# 32-054.net
KiCad netlist of a schematic drawn in Altium Designer
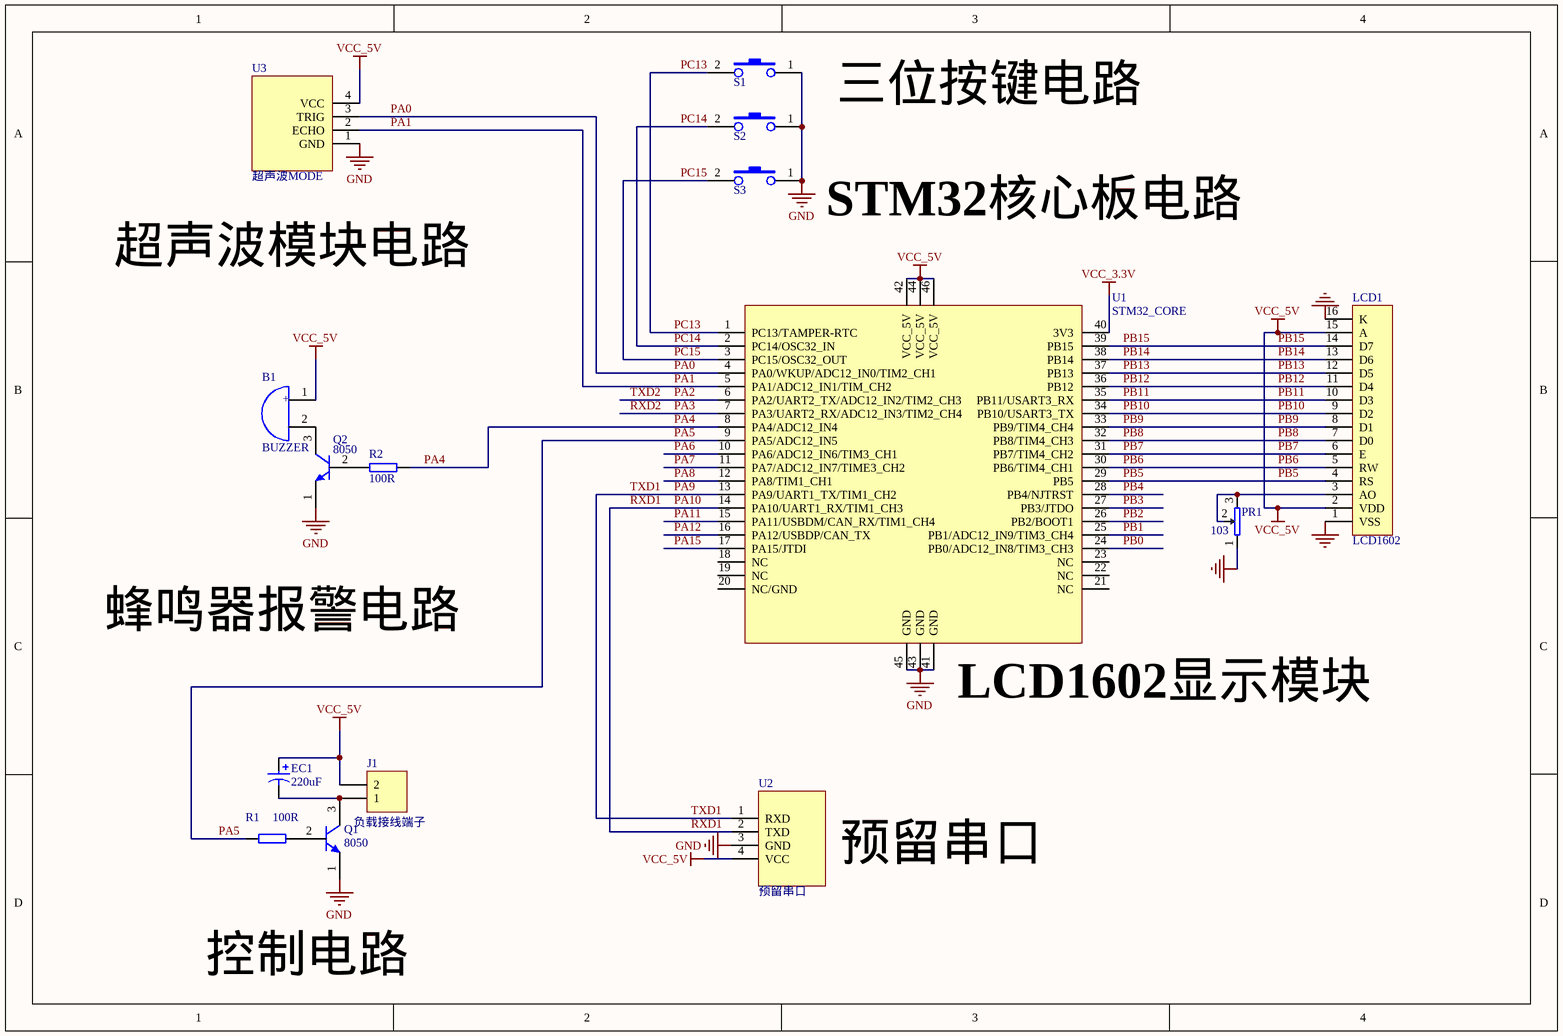
[diagram p0: 32-054原理图（源文件格式）.SchDoc]

(export (version "E")
  (design (tool "Eeschema 10.0.6"))
  (components
    (comp (ref "B1")
      (value "BUZZER")
      (footprint "BUZZERSOT_PLASTIC")
      (description "蜂鸣器")
      (libsource (lib "参考") (part "BUZZER"))
    )
    (comp (ref "EC1")
      (value "220uF")
      (footprint "RB.15/.3")
      (description "极性电容")
      (libsource (lib "参考") (part "CAP_EC"))
    )
    (comp (ref "J1")
      (value "负载接线端子")
      (footprint "XH-2.54-2P")
      (description "接线端子2芯")
      (fields (field (name "PUBLISHER") "Altium Limited"))
      (libsource (lib "参考") (part "CON2"))
    )
    (comp (ref "LCD1")
      (value "LCD1602")
      (footprint "LCD1602")
      (description "LCD1602液晶")
      (libsource (lib "参考") (part "LCD1602"))
    )
    (comp (ref "PR1")
      (value "103")
      (footprint "WH06-2")
      (description "电位器")
      (libsource (lib "参考") (part "PR"))
    )
    (comp (ref "Q1")
      (value "8050")
      (footprint "TO-92")
      (description "三极管")
      (libsource (lib "参考") (part "9013"))
    )
    (comp (ref "Q2")
      (value "8050")
      (footprint "TO-92")
      (description "三极管")
      (libsource (lib "参考") (part "9013"))
    )
    (comp (ref "R1")
      (value "100R")
      (footprint "AXIAL0.3")
      (description "电阻")
      (libsource (lib "参考") (part "RES"))
    )
    (comp (ref "R2")
      (value "100R")
      (footprint "AXIAL0.3")
      (description "电阻")
      (libsource (lib "参考") (part "RES"))
    )
    (comp (ref "S1")
      (value "BUTTOM")
      (footprint "BUTTOM_6x6DIP")
      (description "按键")
      (libsource (lib "参考") (part "BUTTOM"))
    )
    (comp (ref "S2")
      (value "BUTTOM")
      (footprint "BUTTOM_6x6DIP")
      (description "按键")
      (libsource (lib "参考") (part "BUTTOM"))
    )
    (comp (ref "S3")
      (value "BUTTOM")
      (footprint "BUTTOM_6x6DIP")
      (description "按键")
      (libsource (lib "参考") (part "BUTTOM"))
    )
    (comp (ref "U1")
      (value "STM32_CORE")
      (footprint "STM32_CORE")
      (description "STM32核心板")
      (libsource (lib "参考") (part "STM32_CORE"))
    )
    (comp (ref "U2") (value "预留串口") (footprint "蓝牙MODE竖放") (libsource (lib "参考") (part "蓝牙MODE")))
    (comp (ref "U3")
      (value "超声波MODE")
      (footprint "超声波MODE")
      (description "超声波模块")
      (libsource (lib "参考") (part "超声波MODE"))
    )
  )
  (nets
    (net (code "1") (name "/PA0") (class "Default")
      (node (ref "U1") (pin "4") (pinfunction "PA0/WKUP/ADC12_IN0/TIM2_CH1_4") (pintype "passive"))
      (node (ref "U3") (pin "3") (pinfunction "TRIG_3") (pintype "passive"))
    )
    (net (code "2") (name "/PA1") (class "Default")
      (node (ref "U1") (pin "5") (pinfunction "PA1/ADC12_IN1/TIM_CH2_5") (pintype "passive"))
      (node (ref "U3") (pin "2") (pinfunction "ECHO_2") (pintype "passive"))
    )
    (net (code "3") (name "/PA2") (class "Default")
      (node (ref "U1") (pin "6") (pinfunction "PA2/UART2_TX/ADC12_IN2/TIM2_CH3_6") (pintype "passive"))
    )
    (net (code "4") (name "/PA3") (class "Default")
      (node (ref "U1") (pin "7") (pinfunction "PA3/UART2_RX/ADC12_IN3/TIM2_CH4_7") (pintype "passive"))
    )
    (net (code "5") (name "/PA4") (class "Default")
      (node (ref "R2") (pin "2") (pinfunction "2_2") (pintype "passive"))
      (node (ref "U1") (pin "8") (pinfunction "PA4/ADC12_IN4_8") (pintype "passive"))
    )
    (net (code "6") (name "/PA5") (class "Default")
      (node (ref "R1") (pin "2") (pinfunction "2_2") (pintype "passive"))
      (node (ref "U1") (pin "9") (pinfunction "PA5/ADC12_IN5_9") (pintype "passive"))
    )
    (net (code "7") (name "/PA6") (class "Default")
      (node (ref "U1") (pin "10") (pinfunction "PA6/ADC12_IN6/TIM3_CH1_10") (pintype "passive"))
    )
    (net (code "8") (name "/PA7") (class "Default")
      (node (ref "U1") (pin "11") (pinfunction "PA7/ADC12_IN7/TIME3_CH2_11") (pintype "passive"))
    )
    (net (code "9") (name "/PA8") (class "Default")
      (node (ref "U1") (pin "12") (pinfunction "PA8/TIM1_CH1_12") (pintype "passive"))
    )
    (net (code "10") (name "/PA9") (class "Default")
      (node (ref "U1") (pin "13") (pinfunction "PA9/UART1_TX/TIM1_CH2_13") (pintype "passive"))
      (node (ref "U2") (pin "1") (pinfunction "RXD_1") (pintype "passive"))
    )
    (net (code "11") (name "/PA10") (class "Default")
      (node (ref "U1") (pin "14") (pinfunction "PA10/UART1_RX/TIM1_CH3_14") (pintype "passive"))
      (node (ref "U2") (pin "2") (pinfunction "TXD_2") (pintype "passive"))
    )
    (net (code "12") (name "/PA11") (class "Default")
      (node (ref "U1") (pin "15") (pinfunction "PA11/USBDM/CAN_RX/TIM1_CH4_15") (pintype "passive"))
    )
    (net (code "13") (name "/PA12") (class "Default")
      (node (ref "U1") (pin "16") (pinfunction "PA12/USBDP/CAN_TX_16") (pintype "passive"))
    )
    (net (code "14") (name "/PA15") (class "Default")
      (node (ref "U1") (pin "17") (pinfunction "PA15/JTDI_17") (pintype "passive"))
    )
    (net (code "15") (name "/PB0") (class "Default")
      (node (ref "U1") (pin "24") (pinfunction "PB0/ADC12_IN8/TIM3_CH3_24") (pintype "passive"))
    )
    (net (code "16") (name "/PB1") (class "Default")
      (node (ref "U1") (pin "25") (pinfunction "PB1/ADC12_IN9/TIM3_CH4_25") (pintype "passive"))
    )
    (net (code "17") (name "/PB2") (class "Default")
      (node (ref "U1") (pin "26") (pinfunction "PB2/BOOT1_26") (pintype "passive"))
    )
    (net (code "18") (name "/PB3") (class "Default")
      (node (ref "U1") (pin "27") (pinfunction "PB3/JTDO_27") (pintype "passive"))
    )
    (net (code "19") (name "/PB4") (class "Default")
      (node (ref "U1") (pin "28") (pinfunction "PB4/NJTRST_28") (pintype "passive"))
    )
    (net (code "20") (name "/PB5") (class "Default")
      (node (ref "LCD1") (pin "4") (pinfunction "RS_4") (pintype "passive"))
      (node (ref "U1") (pin "29") (pinfunction "PB5_29") (pintype "passive"))
    )
    (net (code "21") (name "/PB6") (class "Default")
      (node (ref "LCD1") (pin "5") (pinfunction "RW_5") (pintype "passive"))
      (node (ref "U1") (pin "30") (pinfunction "PB6/TIM4_CH1_30") (pintype "passive"))
    )
    (net (code "22") (name "/PB7") (class "Default")
      (node (ref "LCD1") (pin "6") (pinfunction "E_6") (pintype "passive"))
      (node (ref "U1") (pin "31") (pinfunction "PB7/TIM4_CH2_31") (pintype "passive"))
    )
    (net (code "23") (name "/PB8") (class "Default")
      (node (ref "LCD1") (pin "7") (pinfunction "D0_7") (pintype "passive"))
      (node (ref "U1") (pin "32") (pinfunction "PB8/TIM4_CH3_32") (pintype "passive"))
    )
    (net (code "24") (name "/PB9") (class "Default")
      (node (ref "LCD1") (pin "8") (pinfunction "D1_8") (pintype "passive"))
      (node (ref "U1") (pin "33") (pinfunction "PB9/TIM4_CH4_33") (pintype "passive"))
    )
    (net (code "25") (name "/PB10") (class "Default")
      (node (ref "LCD1") (pin "9") (pinfunction "D2_9") (pintype "passive"))
      (node (ref "U1") (pin "34") (pinfunction "PB10/USART3_TX_34") (pintype "passive"))
    )
    (net (code "26") (name "/PB11") (class "Default")
      (node (ref "LCD1") (pin "10") (pinfunction "D3_10") (pintype "passive"))
      (node (ref "U1") (pin "35") (pinfunction "PB11/USART3_RX_35") (pintype "passive"))
    )
    (net (code "27") (name "/PB12") (class "Default")
      (node (ref "LCD1") (pin "11") (pinfunction "D4_11") (pintype "passive"))
      (node (ref "U1") (pin "36") (pinfunction "PB12_36") (pintype "passive"))
    )
    (net (code "28") (name "/PB13") (class "Default")
      (node (ref "LCD1") (pin "12") (pinfunction "D5_12") (pintype "passive"))
      (node (ref "U1") (pin "37") (pinfunction "PB13_37") (pintype "passive"))
    )
    (net (code "29") (name "/PB14") (class "Default")
      (node (ref "LCD1") (pin "13") (pinfunction "D6_13") (pintype "passive"))
      (node (ref "U1") (pin "38") (pinfunction "PB14_38") (pintype "passive"))
    )
    (net (code "30") (name "/PB15") (class "Default")
      (node (ref "LCD1") (pin "14") (pinfunction "D7_14") (pintype "passive"))
      (node (ref "U1") (pin "39") (pinfunction "PB15_39") (pintype "passive"))
    )
    (net (code "31") (name "/PC13") (class "Default")
      (node (ref "S1") (pin "2") (pinfunction "2_2") (pintype "passive"))
      (node (ref "U1") (pin "1") (pinfunction "PC13/TAMPER-RTC_1") (pintype "passive"))
    )
    (net (code "32") (name "/PC14") (class "Default")
      (node (ref "S2") (pin "2") (pinfunction "2_2") (pintype "passive"))
      (node (ref "U1") (pin "2") (pinfunction "PC14/OSC32_IN_2") (pintype "passive"))
    )
    (net (code "33") (name "/PC15") (class "Default")
      (node (ref "S3") (pin "2") (pinfunction "2_2") (pintype "passive"))
      (node (ref "U1") (pin "3") (pinfunction "PC15/OSC32_OUT_3") (pintype "passive"))
    )
    (net (code "34") (name "GND") (class "Default")
      (node (ref "LCD1") (pin "1") (pinfunction "VSS_1") (pintype "passive"))
      (node (ref "LCD1") (pin "16") (pinfunction "K_16") (pintype "passive"))
      (node (ref "PR1") (pin "1") (pinfunction "1_1") (pintype "passive"))
      (node (ref "Q1") (pin "1") (pinfunction "1_1") (pintype "passive"))
      (node (ref "Q2") (pin "1") (pinfunction "1_1") (pintype "passive"))
      (node (ref "S1") (pin "1") (pinfunction "1_1") (pintype "passive"))
      (node (ref "S2") (pin "1") (pinfunction "1_1") (pintype "passive"))
      (node (ref "S3") (pin "1") (pinfunction "1_1") (pintype "passive"))
      (node (ref "U1") (pin "41") (pinfunction "GND_41") (pintype "passive"))
      (node (ref "U1") (pin "43") (pinfunction "GND_43") (pintype "passive"))
      (node (ref "U1") (pin "45") (pinfunction "GND_45") (pintype "passive"))
      (node (ref "U2") (pin "3") (pinfunction "GND_3") (pintype "passive"))
      (node (ref "U3") (pin "1") (pinfunction "GND_1") (pintype "passive"))
    )
    (net (code "35") (name "Net-(B1-Pad2)") (class "Default")
      (node (ref "B1") (pin "2") (pinfunction "2_2") (pintype "passive"))
      (node (ref "Q2") (pin "3") (pinfunction "3_3") (pintype "passive"))
    )
    (net (code "36") (name "Net-(EC1-Pad2)") (class "Default")
      (node (ref "EC1") (pin "2") (pinfunction "2_2") (pintype "passive"))
      (node (ref "J1") (pin "1") (pinfunction "1_1") (pintype "passive"))
      (node (ref "Q1") (pin "3") (pinfunction "3_3") (pintype "passive"))
    )
    (net (code "37") (name "Net-(LCD1-AO)") (class "Default")
      (node (ref "LCD1") (pin "3") (pinfunction "AO_3") (pintype "passive"))
      (node (ref "PR1") (pin "2") (pinfunction "2_2") (pintype "passive"))
      (node (ref "PR1") (pin "3") (pinfunction "3_3") (pintype "passive"))
    )
    (net (code "38") (name "Net-(Q1-Pad2)") (class "Default")
      (node (ref "Q1") (pin "2") (pinfunction "2_2") (pintype "passive"))
      (node (ref "R1") (pin "1") (pinfunction "1_1") (pintype "passive"))
    )
    (net (code "39") (name "Net-(Q2-Pad2)") (class "Default")
      (node (ref "Q2") (pin "2") (pinfunction "2_2") (pintype "passive"))
      (node (ref "R2") (pin "1") (pinfunction "1_1") (pintype "passive"))
    )
    (net (code "40") (name "VCC_3.3V") (class "Default")
      (node (ref "U1") (pin "40") (pinfunction "3V3_40") (pintype "passive"))
    )
    (net (code "41") (name "VCC_5V") (class "Default")
      (node (ref "B1") (pin "1") (pinfunction "1_1") (pintype "passive"))
      (node (ref "EC1") (pin "1") (pinfunction "1_1") (pintype "passive"))
      (node (ref "J1") (pin "2") (pinfunction "2_2") (pintype "passive"))
      (node (ref "LCD1") (pin "15") (pinfunction "A_15") (pintype "passive"))
      (node (ref "LCD1") (pin "2") (pinfunction "VDD_2") (pintype "passive"))
      (node (ref "U1") (pin "42") (pinfunction "VCC_5V_42") (pintype "passive"))
      (node (ref "U1") (pin "44") (pinfunction "VCC_5V_44") (pintype "passive"))
      (node (ref "U1") (pin "46") (pinfunction "VCC_5V_46") (pintype "passive"))
      (node (ref "U2") (pin "4") (pinfunction "VCC_4") (pintype "passive"))
      (node (ref "U3") (pin "4") (pinfunction "VCC_4") (pintype "passive"))
    )
    (net (code "42") (name "unconnected-(U1-NC-Pad18)") (class "Default")
      (node (ref "U1") (pin "18") (pinfunction "NC_18") (pintype "passive"))
    )
    (net (code "43") (name "unconnected-(U1-NC-Pad19)") (class "Default")
      (node (ref "U1") (pin "19") (pinfunction "NC_19") (pintype "passive"))
    )
    (net (code "44") (name "unconnected-(U1-NC-Pad21)") (class "Default")
      (node (ref "U1") (pin "21") (pinfunction "NC_21") (pintype "passive"))
    )
    (net (code "45") (name "unconnected-(U1-NC-Pad22)") (class "Default")
      (node (ref "U1") (pin "22") (pinfunction "NC_22") (pintype "passive"))
    )
    (net (code "46") (name "unconnected-(U1-NC-Pad23)") (class "Default")
      (node (ref "U1") (pin "23") (pinfunction "NC_23") (pintype "passive"))
    )
    (net (code "47") (name "unconnected-(U1-NC{slash}GND-Pad20)") (class "Default")
      (node (ref "U1") (pin "20") (pinfunction "NC/GND_20") (pintype "passive"))
    )
  )
)
